# MPPT.net
KiCad netlist of a schematic drawn in Altium Designer
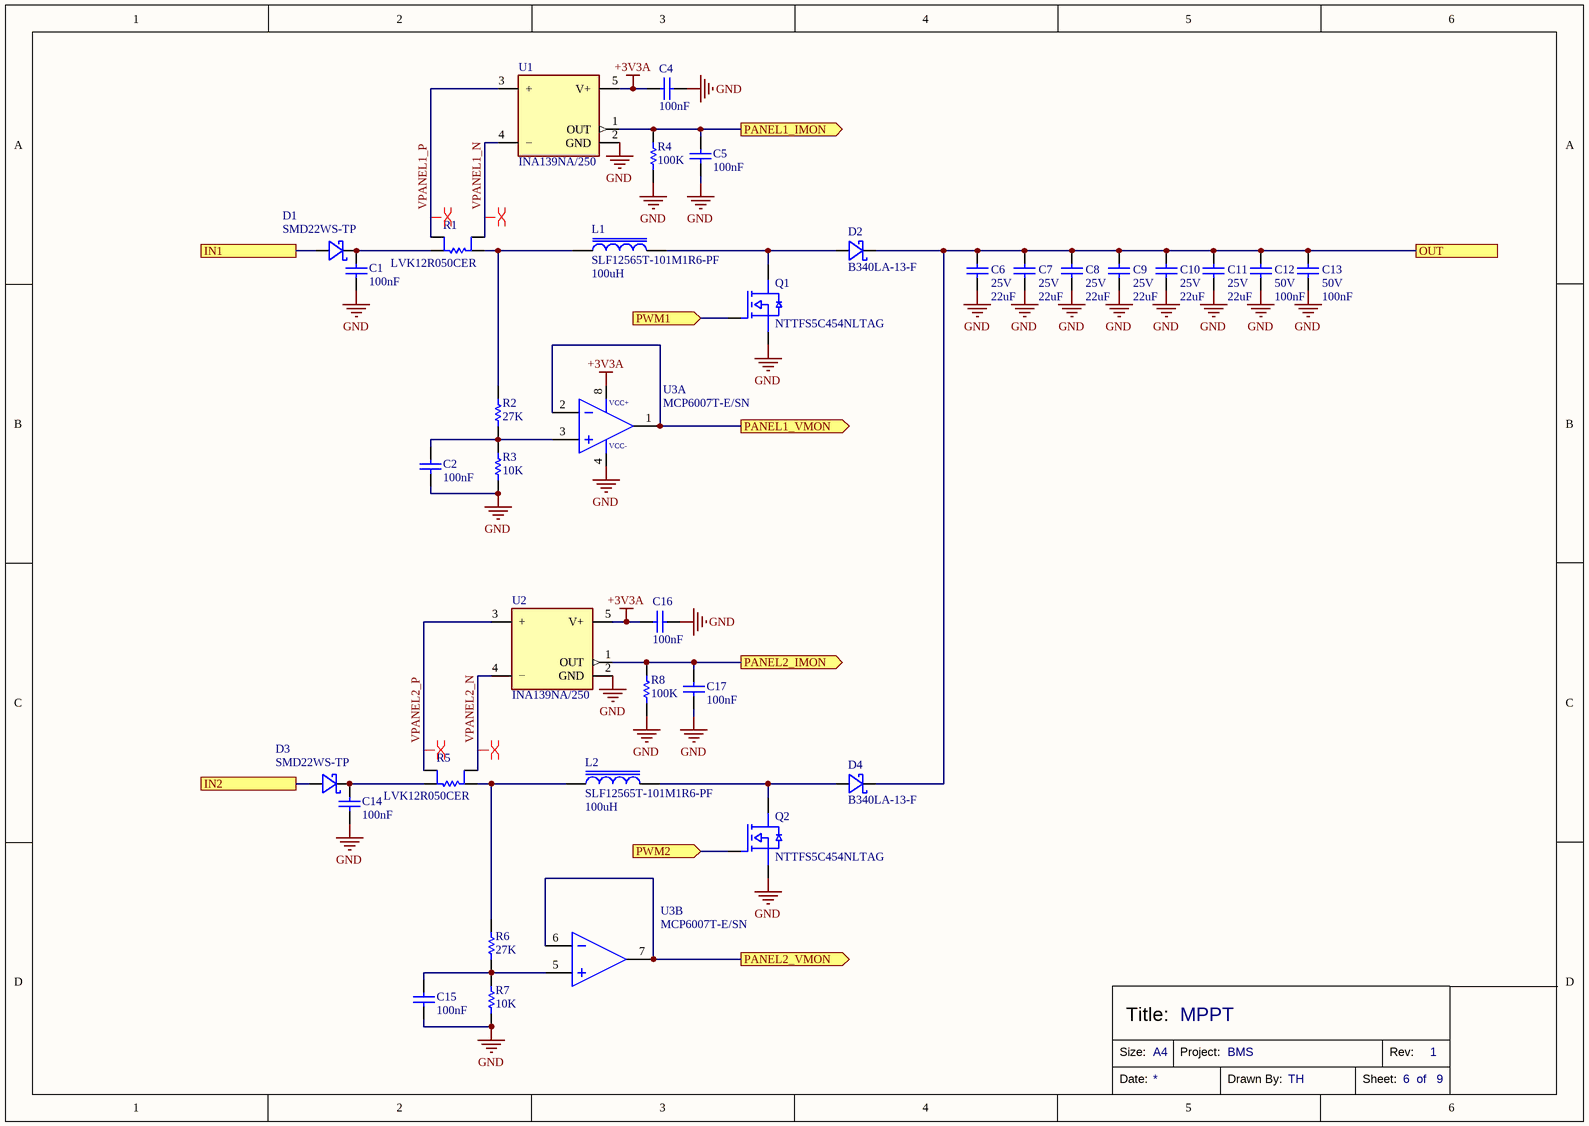
[diagram p0: MPPT.SchDoc]

(export (version "E")
  (design (tool "Eeschema 10.0.6"))
  (components
    (comp (ref "C1")
      (value "C0603C104K5RACTU")
      (footprint "CAPC0603X040")
      (description "0.1 µF ±10% 50V Ceramic Capacitor X7R 0603 (1608 Metric)")
      (fields
        (field (name "DISTRIBUTOR PART NUMBER") "399-C0603C104K5RACTUCT-ND")
        (field (name "TOLERANCE") "10%")
        (field (name "CAPACITANCE") "100nF")
      )
      (libsource (lib "Ahristi_Library") (part "C0603C104K5RACTU"))
    )
    (comp (ref "C2")
      (value "C0603C104K5RACTU")
      (footprint "CAPC0603X040")
      (description "0.1 µF ±10% 50V Ceramic Capacitor X7R 0603 (1608 Metric)")
      (fields
        (field (name "DISTRIBUTOR PART NUMBER") "399-C0603C104K5RACTUCT-ND")
        (field (name "TOLERANCE") "10%")
        (field (name "CAPACITANCE") "100nF")
      )
      (libsource (lib "Ahristi_Library") (part "C0603C104K5RACTU"))
    )
    (comp (ref "C4")
      (value "C0603C104K5RACTU")
      (footprint "CAPC0603X040")
      (description "0.1 µF ±10% 50V Ceramic Capacitor X7R 0603 (1608 Metric)")
      (fields
        (field (name "DISTRIBUTOR PART NUMBER") "399-C0603C104K5RACTUCT-ND")
        (field (name "TOLERANCE") "10%")
        (field (name "CAPACITANCE") "100nF")
      )
      (libsource (lib "Ahristi_Library") (part "C0603C104K5RACTU"))
    )
    (comp (ref "C5")
      (value "C0603C104K5RACTU")
      (footprint "CAPC0603X040")
      (description "0.1 µF ±10% 50V Ceramic Capacitor X7R 0603 (1608 Metric)")
      (fields
        (field (name "DISTRIBUTOR PART NUMBER") "399-C0603C104K5RACTUCT-ND")
        (field (name "TOLERANCE") "10%")
        (field (name "CAPACITANCE") "100nF")
      )
      (libsource (lib "Ahristi_Library") (part "C0603C104K5RACTU"))
    )
    (comp (ref "C6")
      (value "CL32B226KAJNNNE")
      (footprint "CAPC1210X090")
      (description "22 µF ±10% 25V Ceramic Capacitor X7R 1210 (3225 Metric)")
      (fields
        (field (name "DISTRIBUTOR PART NUMBER") "1276-3392-1-ND")
        (field (name "TOLERANCE") "10%")
        (field (name "VOLTAGE RATING") "25V")
        (field (name "CAPACITANCE") "22uF")
      )
      (libsource (lib "Ahristi_Library") (part "CL32B226KAJNNNE"))
    )
    (comp (ref "C7")
      (value "CL32B226KAJNNNE")
      (footprint "CAPC1210X090")
      (description "22 µF ±10% 25V Ceramic Capacitor X7R 1210 (3225 Metric)")
      (fields
        (field (name "DISTRIBUTOR PART NUMBER") "1276-3392-1-ND")
        (field (name "TOLERANCE") "10%")
        (field (name "VOLTAGE RATING") "25V")
        (field (name "CAPACITANCE") "22uF")
      )
      (libsource (lib "Ahristi_Library") (part "CL32B226KAJNNNE"))
    )
    (comp (ref "C8")
      (value "CL32B226KAJNNNE")
      (footprint "CAPC1210X090")
      (description "22 µF ±10% 25V Ceramic Capacitor X7R 1210 (3225 Metric)")
      (fields
        (field (name "DISTRIBUTOR PART NUMBER") "1276-3392-1-ND")
        (field (name "TOLERANCE") "10%")
        (field (name "VOLTAGE RATING") "25V")
        (field (name "CAPACITANCE") "22uF")
      )
      (libsource (lib "Ahristi_Library") (part "CL32B226KAJNNNE"))
    )
    (comp (ref "C9")
      (value "CL32B226KAJNNNE")
      (footprint "CAPC1210X090")
      (description "22 µF ±10% 25V Ceramic Capacitor X7R 1210 (3225 Metric)")
      (fields
        (field (name "DISTRIBUTOR PART NUMBER") "1276-3392-1-ND")
        (field (name "TOLERANCE") "10%")
        (field (name "VOLTAGE RATING") "25V")
        (field (name "CAPACITANCE") "22uF")
      )
      (libsource (lib "Ahristi_Library") (part "CL32B226KAJNNNE"))
    )
    (comp (ref "C10")
      (value "CL32B226KAJNNNE")
      (footprint "CAPC1210X090")
      (description "22 µF ±10% 25V Ceramic Capacitor X7R 1210 (3225 Metric)")
      (fields
        (field (name "DISTRIBUTOR PART NUMBER") "1276-3392-1-ND")
        (field (name "TOLERANCE") "10%")
        (field (name "VOLTAGE RATING") "25V")
        (field (name "CAPACITANCE") "22uF")
      )
      (libsource (lib "Ahristi_Library") (part "CL32B226KAJNNNE"))
    )
    (comp (ref "C11")
      (value "CL32B226KAJNNNE")
      (footprint "CAPC1210X090")
      (description "22 µF ±10% 25V Ceramic Capacitor X7R 1210 (3225 Metric)")
      (fields
        (field (name "DISTRIBUTOR PART NUMBER") "1276-3392-1-ND")
        (field (name "TOLERANCE") "10%")
        (field (name "VOLTAGE RATING") "25V")
        (field (name "CAPACITANCE") "22uF")
      )
      (libsource (lib "Ahristi_Library") (part "CL32B226KAJNNNE"))
    )
    (comp (ref "C12")
      (value "C0603C104K5RACTU")
      (footprint "CAPC0603X040")
      (description "0.1 µF ±10% 50V Ceramic Capacitor X7R 0603 (1608 Metric)")
      (fields
        (field (name "DISTRIBUTOR PART NUMBER") "399-C0603C104K5RACTUCT-ND")
        (field (name "TOLERANCE") "10%")
        (field (name "VOLTAGE RATING") "50V")
        (field (name "CAPACITANCE") "100nF")
      )
      (libsource (lib "Ahristi_Library") (part "C0603C104K5RACTU"))
    )
    (comp (ref "C13")
      (value "C0603C104K5RACTU")
      (footprint "CAPC0603X040")
      (description "0.1 µF ±10% 50V Ceramic Capacitor X7R 0603 (1608 Metric)")
      (fields
        (field (name "DISTRIBUTOR PART NUMBER") "399-C0603C104K5RACTUCT-ND")
        (field (name "TOLERANCE") "10%")
        (field (name "VOLTAGE RATING") "50V")
        (field (name "CAPACITANCE") "100nF")
      )
      (libsource (lib "Ahristi_Library") (part "C0603C104K5RACTU"))
    )
    (comp (ref "C14")
      (value "C0603C104K5RACTU")
      (footprint "CAPC0603X040")
      (description "0.1 µF ±10% 50V Ceramic Capacitor X7R 0603 (1608 Metric)")
      (fields
        (field (name "DISTRIBUTOR PART NUMBER") "399-C0603C104K5RACTUCT-ND")
        (field (name "TOLERANCE") "10%")
        (field (name "CAPACITANCE") "100nF")
      )
      (libsource (lib "Ahristi_Library") (part "C0603C104K5RACTU"))
    )
    (comp (ref "C15")
      (value "C0603C104K5RACTU")
      (footprint "CAPC0603X040")
      (description "0.1 µF ±10% 50V Ceramic Capacitor X7R 0603 (1608 Metric)")
      (fields
        (field (name "DISTRIBUTOR PART NUMBER") "399-C0603C104K5RACTUCT-ND")
        (field (name "TOLERANCE") "10%")
        (field (name "CAPACITANCE") "100nF")
      )
      (libsource (lib "Ahristi_Library") (part "C0603C104K5RACTU"))
    )
    (comp (ref "C16")
      (value "C0603C104K5RACTU")
      (footprint "CAPC0603X040")
      (description "0.1 µF ±10% 50V Ceramic Capacitor X7R 0603 (1608 Metric)")
      (fields
        (field (name "DISTRIBUTOR PART NUMBER") "399-C0603C104K5RACTUCT-ND")
        (field (name "TOLERANCE") "10%")
        (field (name "CAPACITANCE") "100nF")
      )
      (libsource (lib "Ahristi_Library") (part "C0603C104K5RACTU"))
    )
    (comp (ref "C17")
      (value "C0603C104K5RACTU")
      (footprint "CAPC0603X040")
      (description "0.1 µF ±10% 50V Ceramic Capacitor X7R 0603 (1608 Metric)")
      (fields
        (field (name "DISTRIBUTOR PART NUMBER") "399-C0603C104K5RACTUCT-ND")
        (field (name "TOLERANCE") "10%")
        (field (name "CAPACITANCE") "100nF")
      )
      (libsource (lib "Ahristi_Library") (part "C0603C104K5RACTU"))
    )
    (comp (ref "D1")
      (value "SMD22WS-TP")
      (footprint "SOD-323")
      (description "Diode Schottky 20V 2A Fast Recovery")
      (fields (field (name "DISTRIBUTOR PART NUMBER") "SMD22WS-TPMSCT-ND"))
      (libsource (lib "Ahristi_Library") (part "SMD22WS-TP"))
    )
    (comp (ref "D2")
      (value "B340LA-13-F")
      (footprint "DO-214")
      (description "Diode Schottky 40V 3A 450mV FVf Fast Recovery")
      (fields (field (name "DISTRIBUTOR PART NUMBER") "B340LA-FDICT-ND"))
      (libsource (lib "Ahristi_Library") (part "B340LA-13-F"))
    )
    (comp (ref "D3")
      (value "SMD22WS-TP")
      (footprint "SOD-323")
      (description "Diode Schottky 20V 2A Fast Recovery")
      (fields (field (name "DISTRIBUTOR PART NUMBER") "SMD22WS-TPMSCT-ND"))
      (libsource (lib "Ahristi_Library") (part "SMD22WS-TP"))
    )
    (comp (ref "D4")
      (value "B340LA-13-F")
      (footprint "DO-214")
      (description "Diode Schottky 40V 3A 450mV FVf Fast Recovery")
      (fields (field (name "DISTRIBUTOR PART NUMBER") "B340LA-FDICT-ND"))
      (libsource (lib "Ahristi_Library") (part "B340LA-13-F"))
    )
    (comp (ref "L1")
      (value "SLF12565T-101M1R6-PF")
      (footprint "SLF12565T-101M1R6-PF")
      (description "Inductor 100uH Shielded Drum Core, 1.9A 148mOhm")
      (fields (field (name "DISTRIBUTOR PART NUMBER") "445-174227-1-ND") (field (name "INDUCTANCE") "100uH"))
      (libsource (lib "Ahristi_Library") (part "SLF12565T-101M1R6-PF"))
    )
    (comp (ref "L2")
      (value "SLF12565T-101M1R6-PF")
      (footprint "SLF12565T-101M1R6-PF")
      (description "Inductor 100uH Shielded Drum Core, 1.9A 148mOhm")
      (fields (field (name "DISTRIBUTOR PART NUMBER") "445-174227-1-ND") (field (name "INDUCTANCE") "100uH"))
      (libsource (lib "Ahristi_Library") (part "SLF12565T-101M1R6-PF"))
    )
    (comp (ref "Q1")
      (value "NTTFS5C454NLTAG")
      (footprint "NTTFS5C454NLTAG")
      (description "N-MOSFET 40 V , 85 A, 3.8 mΩ Rds(on) @ 10 V, WDFN-8 3.3×3.3 mm, low Qg (~18 nC)")
      (fields
        (field (name "PART NUMBER") "NTTFS5C454NL")
        (field (name "DISTRIBUTOR PART NUMBER") "863-NTTFS5C454NLTAG")
      )
      (libsource (lib "Ahristi_Library") (part "NTTFS5C454NLTAG"))
    )
    (comp (ref "Q2")
      (value "NTTFS5C454NLTAG")
      (footprint "NTTFS5C454NLTAG")
      (description "N-MOSFET 40 V , 85 A, 3.8 mΩ Rds(on) @ 10 V, WDFN-8 3.3×3.3 mm, low Qg (~18 nC)")
      (fields
        (field (name "PART NUMBER") "NTTFS5C454NL")
        (field (name "DISTRIBUTOR PART NUMBER") "863-NTTFS5C454NLTAG")
      )
      (libsource (lib "Ahristi_Library") (part "NTTFS5C454NLTAG"))
    )
    (comp (ref "R1")
      (value "LVK12R050CER")
      (footprint "LVK12R050CER-1")
      (description "Resistor, Current Sense 50 mOhms ±0.25% 0.5W, Moisture Resistant Thick Film")
      (fields
        (field (name "DISTRIBUTOR PART NUMBER") "588-LVK12R050CER")
        (field (name "MANUFACTURER") "Ohmite")
      )
      (libsource (lib "Ahristi_Library") (part "LVK12R050CER"))
    )
    (comp (ref "R2")
      (value "RMCF0603FT27K0")
      (footprint "RESC0603")
      (description "27 kOhms ±1% 0.1W, 1/10W Chip Resistor 0603 (1608 Metric) Automotive AEC-Q200 Thick Film")
      (fields
        (field (name "TOLERANCE") "1%")
        (field (name "DISTRIBUTOR PART NUMBER") "RMCF0603FT27K0CT-ND")
        (field (name "RESISTANCE") "27K")
      )
      (libsource (lib "Ahristi_Library") (part "RMCF0603FT27K0"))
    )
    (comp (ref "R3")
      (value "RMCF0603FT10K0")
      (footprint "RESC0603")
      (description "10 kOhms ±1% 0.1W, 1/10W Chip Resistor 0603 (1608 Metric) Automotive AEC-Q200 Thick Film")
      (fields
        (field (name "TOLERANCE") "1%")
        (field (name "DISTRIBUTOR PART NUMBER") "RMCF0603FT10K0CT-ND")
        (field (name "RESISTANCE") "10K")
      )
      (libsource (lib "Ahristi_Library") (part "RMCF0603FT10K0"))
    )
    (comp (ref "R4")
      (value "RMCF0603FT100K")
      (footprint "RESC0603")
      (description "100 kOhms ±1% 0.1W, 1/10W Chip Resistor 0603 (1608 Metric) Automotive AEC-Q200 Thick Film")
      (fields
        (field (name "TOLERANCE") "1%")
        (field (name "DISTRIBUTOR PART NUMBER") "RMCF0603FT100KCT-ND")
        (field (name "RESISTANCE") "100K")
      )
      (libsource (lib "Ahristi_Library") (part "RMCF0603FT100K"))
    )
    (comp (ref "R5")
      (value "LVK12R050CER")
      (footprint "LVK12R050CER-2")
      (description "Resistor, Current Sense 50 mOhms ±0.25% 0.5W, Moisture Resistant Thick Film")
      (fields
        (field (name "DISTRIBUTOR PART NUMBER") "588-LVK12R050CER")
        (field (name "MANUFACTURER") "Ohmite")
      )
      (libsource (lib "Ahristi_Library") (part "LVK12R050CER"))
    )
    (comp (ref "R6")
      (value "RMCF0603FT27K0")
      (footprint "RESC0603")
      (description "27 kOhms ±1% 0.1W, 1/10W Chip Resistor 0603 (1608 Metric) Automotive AEC-Q200 Thick Film")
      (fields
        (field (name "TOLERANCE") "1%")
        (field (name "DISTRIBUTOR PART NUMBER") "RMCF0603FT27K0CT-ND")
        (field (name "RESISTANCE") "27K")
      )
      (libsource (lib "Ahristi_Library") (part "RMCF0603FT27K0"))
    )
    (comp (ref "R7")
      (value "RMCF0603FT10K0")
      (footprint "RESC0603")
      (description "10 kOhms ±1% 0.1W, 1/10W Chip Resistor 0603 (1608 Metric) Automotive AEC-Q200 Thick Film")
      (fields
        (field (name "TOLERANCE") "1%")
        (field (name "DISTRIBUTOR PART NUMBER") "RMCF0603FT10K0CT-ND")
        (field (name "RESISTANCE") "10K")
      )
      (libsource (lib "Ahristi_Library") (part "RMCF0603FT10K0"))
    )
    (comp (ref "R8")
      (value "RMCF0603FT100K")
      (footprint "RESC0603")
      (description "100 kOhms ±1% 0.1W, 1/10W Chip Resistor 0603 (1608 Metric) Automotive AEC-Q200 Thick Film")
      (fields
        (field (name "TOLERANCE") "1%")
        (field (name "DISTRIBUTOR PART NUMBER") "RMCF0603FT100KCT-ND")
        (field (name "RESISTANCE") "100K")
      )
      (libsource (lib "Ahristi_Library") (part "RMCF0603FT100K"))
    )
    (comp (ref "U1")
      (value "INA139NA/250")
      (footprint "SOT23-5 IC")
      (description "40V Current Sense Amplifier 1 Circuit 8-MSOP")
      (fields (field (name "DISTRIBUTOR PART NUMBER") "INA139NA/250CT-ND"))
      (libsource (lib "Ahristi_Library") (part "INA139NA/250"))
    )
    (comp (ref "U2")
      (value "INA139NA/250")
      (footprint "SOT23-5 IC")
      (description "40V Current Sense Amplifier 1 Circuit 8-MSOP")
      (fields (field (name "DISTRIBUTOR PART NUMBER") "INA139NA/250CT-ND"))
      (libsource (lib "Ahristi_Library") (part "INA139NA/250"))
    )
    (comp (ref "U3")
      (value "MCP6007T-E/SN")
      (footprint "SOIC-8")
      (description "Operational Amplifier general purpose, 2-Circuit 1.8V ~ 5.5V 1MHz")
      (fields (field (name "DISTRIBUTOR PART NUMBER") "150-MCP6007T-E/SNCT-ND"))
      (libsource (lib "Ahristi_Library") (part "MCP6007T-E/SN"))
    )
  )
  (nets
    (net (code "1") (name "+3V3A") (class "Default")
      (node (ref "C16") (pin "2") (pinfunction "2_2") (pintype "passive"))
      (node (ref "C4") (pin "2") (pinfunction "2_2") (pintype "passive"))
      (node (ref "U1") (pin "5") (pinfunction "V+_5") (pintype "passive"))
      (node (ref "U2") (pin "5") (pinfunction "V+_5") (pintype "passive"))
      (node (ref "U3") (pin "8") (pinfunction "VCC+_8") (pintype "passive"))
    )
    (net (code "2") (name "/IN1") (class "Default")
      (node (ref "D1") (pin "A") (pinfunction "A_A") (pintype "passive"))
    )
    (net (code "3") (name "/IN2") (class "Default")
      (node (ref "D3") (pin "A") (pinfunction "A_A") (pintype "passive"))
    )
    (net (code "4") (name "/OUT") (class "Default")
      (node (ref "C10") (pin "2") (pinfunction "2_2") (pintype "passive"))
      (node (ref "C11") (pin "2") (pinfunction "2_2") (pintype "passive"))
      (node (ref "C12") (pin "2") (pinfunction "2_2") (pintype "passive"))
      (node (ref "C13") (pin "2") (pinfunction "2_2") (pintype "passive"))
      (node (ref "C6") (pin "2") (pinfunction "2_2") (pintype "passive"))
      (node (ref "C7") (pin "2") (pinfunction "2_2") (pintype "passive"))
      (node (ref "C8") (pin "2") (pinfunction "2_2") (pintype "passive"))
      (node (ref "C9") (pin "2") (pinfunction "2_2") (pintype "passive"))
      (node (ref "D2") (pin "K") (pinfunction "K_K") (pintype "passive"))
      (node (ref "D4") (pin "K") (pinfunction "K_K") (pintype "passive"))
    )
    (net (code "5") (name "/PANEL1_IMON") (class "Default")
      (node (ref "C5") (pin "2") (pinfunction "2_2") (pintype "passive"))
      (node (ref "R4") (pin "2") (pinfunction "2_2") (pintype "passive"))
      (node (ref "U1") (pin "1") (pinfunction "OUT_1") (pintype "output"))
    )
    (net (code "6") (name "/PANEL1_VMON") (class "Default")
      (node (ref "U3") (pin "1") (pinfunction "OUTA_1") (pintype "passive"))
      (node (ref "U3") (pin "2") (pinfunction "INA-_2") (pintype "passive"))
    )
    (net (code "7") (name "/PANEL2_IMON") (class "Default")
      (node (ref "C17") (pin "2") (pinfunction "2_2") (pintype "passive"))
      (node (ref "R8") (pin "2") (pinfunction "2_2") (pintype "passive"))
      (node (ref "U2") (pin "1") (pinfunction "OUT_1") (pintype "output"))
    )
    (net (code "8") (name "/PANEL2_VMON") (class "Default")
      (node (ref "U3") (pin "6") (pinfunction "INB-_6") (pintype "passive"))
      (node (ref "U3") (pin "7") (pinfunction "OUTB_7") (pintype "passive"))
    )
    (net (code "9") (name "/PWM1") (class "Default")
      (node (ref "Q1") (pin "G") (pinfunction "G_G") (pintype "passive"))
    )
    (net (code "10") (name "/PWM2") (class "Default")
      (node (ref "Q2") (pin "G") (pinfunction "G_G") (pintype "passive"))
    )
    (net (code "11") (name "/VPANEL1_N") (class "Default")
      (node (ref "R1") (pin "3") (pinfunction "3_3") (pintype "passive"))
      (node (ref "U1") (pin "4") (pinfunction "−_4") (pintype "passive"))
    )
    (net (code "12") (name "/VPANEL1_P") (class "Default")
      (node (ref "R1") (pin "2") (pinfunction "2_2") (pintype "passive"))
      (node (ref "U1") (pin "3") (pinfunction "+_3") (pintype "passive"))
    )
    (net (code "13") (name "/VPANEL2_N") (class "Default")
      (node (ref "R5") (pin "3") (pinfunction "3_3") (pintype "passive"))
      (node (ref "U2") (pin "4") (pinfunction "−_4") (pintype "passive"))
    )
    (net (code "14") (name "/VPANEL2_P") (class "Default")
      (node (ref "R5") (pin "2") (pinfunction "2_2") (pintype "passive"))
      (node (ref "U2") (pin "3") (pinfunction "+_3") (pintype "passive"))
    )
    (net (code "15") (name "GND") (class "Default")
      (node (ref "C1") (pin "1") (pinfunction "1_1") (pintype "passive"))
      (node (ref "C10") (pin "1") (pinfunction "1_1") (pintype "passive"))
      (node (ref "C11") (pin "1") (pinfunction "1_1") (pintype "passive"))
      (node (ref "C12") (pin "1") (pinfunction "1_1") (pintype "passive"))
      (node (ref "C13") (pin "1") (pinfunction "1_1") (pintype "passive"))
      (node (ref "C14") (pin "1") (pinfunction "1_1") (pintype "passive"))
      (node (ref "C15") (pin "1") (pinfunction "1_1") (pintype "passive"))
      (node (ref "C16") (pin "1") (pinfunction "1_1") (pintype "passive"))
      (node (ref "C17") (pin "1") (pinfunction "1_1") (pintype "passive"))
      (node (ref "C2") (pin "1") (pinfunction "1_1") (pintype "passive"))
      (node (ref "C4") (pin "1") (pinfunction "1_1") (pintype "passive"))
      (node (ref "C5") (pin "1") (pinfunction "1_1") (pintype "passive"))
      (node (ref "C6") (pin "1") (pinfunction "1_1") (pintype "passive"))
      (node (ref "C7") (pin "1") (pinfunction "1_1") (pintype "passive"))
      (node (ref "C8") (pin "1") (pinfunction "1_1") (pintype "passive"))
      (node (ref "C9") (pin "1") (pinfunction "1_1") (pintype "passive"))
      (node (ref "Q1") (pin "S") (pinfunction "S_S") (pintype "passive"))
      (node (ref "Q2") (pin "S") (pinfunction "S_S") (pintype "passive"))
      (node (ref "R3") (pin "1") (pinfunction "1_1") (pintype "passive"))
      (node (ref "R4") (pin "1") (pinfunction "1_1") (pintype "passive"))
      (node (ref "R7") (pin "1") (pinfunction "1_1") (pintype "passive"))
      (node (ref "R8") (pin "1") (pinfunction "1_1") (pintype "passive"))
      (node (ref "U1") (pin "2") (pinfunction "GND_2") (pintype "passive"))
      (node (ref "U2") (pin "2") (pinfunction "GND_2") (pintype "passive"))
      (node (ref "U3") (pin "4") (pinfunction "VCC-_4") (pintype "passive"))
    )
    (net (code "16") (name "Net-(C1-Pad2)") (class "Default")
      (node (ref "C1") (pin "2") (pinfunction "2_2") (pintype "passive"))
      (node (ref "D1") (pin "K") (pinfunction "K_K") (pintype "passive"))
      (node (ref "R1") (pin "1") (pinfunction "1_1") (pintype "passive"))
    )
    (net (code "17") (name "Net-(C14-Pad2)") (class "Default")
      (node (ref "C14") (pin "2") (pinfunction "2_2") (pintype "passive"))
      (node (ref "D3") (pin "K") (pinfunction "K_K") (pintype "passive"))
      (node (ref "R5") (pin "1") (pinfunction "1_1") (pintype "passive"))
    )
    (net (code "18") (name "Net-(D2-PadA)") (class "Default")
      (node (ref "D2") (pin "A") (pinfunction "A_A") (pintype "passive"))
      (node (ref "L1") (pin "1") (pinfunction "1_1") (pintype "passive"))
      (node (ref "Q1") (pin "D") (pinfunction "D_D") (pintype "passive"))
    )
    (net (code "19") (name "Net-(D4-PadA)") (class "Default")
      (node (ref "D4") (pin "A") (pinfunction "A_A") (pintype "passive"))
      (node (ref "L2") (pin "1") (pinfunction "1_1") (pintype "passive"))
      (node (ref "Q2") (pin "D") (pinfunction "D_D") (pintype "passive"))
    )
    (net (code "20") (name "Net-(L1-Pad2)") (class "Default")
      (node (ref "L1") (pin "2") (pinfunction "2_2") (pintype "passive"))
      (node (ref "R1") (pin "4") (pinfunction "4_4") (pintype "passive"))
      (node (ref "R2") (pin "2") (pinfunction "2_2") (pintype "passive"))
    )
    (net (code "21") (name "Net-(L2-Pad2)") (class "Default")
      (node (ref "L2") (pin "2") (pinfunction "2_2") (pintype "passive"))
      (node (ref "R5") (pin "4") (pinfunction "4_4") (pintype "passive"))
      (node (ref "R6") (pin "2") (pinfunction "2_2") (pintype "passive"))
    )
    (net (code "22") (name "Net-(U3A-INA+)") (class "Default")
      (node (ref "C2") (pin "2") (pinfunction "2_2") (pintype "passive"))
      (node (ref "R2") (pin "1") (pinfunction "1_1") (pintype "passive"))
      (node (ref "R3") (pin "2") (pinfunction "2_2") (pintype "passive"))
      (node (ref "U3") (pin "3") (pinfunction "INA+_3") (pintype "passive"))
    )
    (net (code "23") (name "Net-(U3B-INB+)") (class "Default")
      (node (ref "C15") (pin "2") (pinfunction "2_2") (pintype "passive"))
      (node (ref "R6") (pin "1") (pinfunction "1_1") (pintype "passive"))
      (node (ref "R7") (pin "2") (pinfunction "2_2") (pintype "passive"))
      (node (ref "U3") (pin "5") (pinfunction "INB+_5") (pintype "passive"))
    )
  )
)
